# Power_Entry_24v-3pin_Fused-1A5.net
KiCad netlist of a schematic drawn in Altium Designer
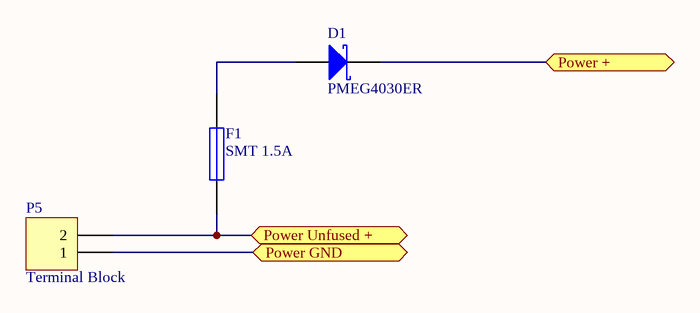
[diagram p0: Power Entry 24v-3pin Fused-1A5.SchDoc]

(export (version "E")
  (design (tool "Eeschema 10.0.6"))
  (components
    (comp (ref "D1")
      (value "PMEG4030ER")
      (footprint "SOD123W")
      (fields (field (name "VOLTAGE") "40V") (field (name "AUTHOR") "Willem Pietersz"))
      (libsource (lib "OurDb") (part "SCHOTTKY"))
    )
    (comp (ref "F1")
      (value "SMT 1.5A")
      (footprint "F_2920L185")
      (description "Fuse")
      (fields
        (field (name "PART NUMBER") "2920L185")
        (field (name "VOLTAGE") "30V")
        (field (name "PUBLISHER") "Altium Limited")
      )
      (libsource (lib "OurDb") (part "Fuse 1"))
    )
    (comp (ref "P5")
      (value "Terminal Block")
      (footprint "TB2_3.5")
      (description "Con1x2")
      (fields
        (field (name "PART NUMBER") "TB2")
        (field (name "VOLTAGE") "300")
        (field (name "AUTHOR") "Willy Pietersz")
      )
      (libsource (lib "OurDb") (part "Con1x2"))
    )
  )
  (nets
    (net (code "1") (name "/Power +") (class "Default")
      (node (ref "D1") (pin "2") (pinfunction "2_2") (pintype "passive"))
    )
    (net (code "2") (name "/Power GND") (class "Default")
      (node (ref "P5") (pin "1") (pinfunction "1_1") (pintype "passive"))
    )
    (net (code "3") (name "/Power Unfused +") (class "Default")
      (node (ref "F1") (pin "1") (pinfunction "1_1") (pintype "passive"))
      (node (ref "P5") (pin "2") (pinfunction "2_2") (pintype "passive"))
    )
    (net (code "4") (name "Net-(D1-Pad1)") (class "Default")
      (node (ref "D1") (pin "1") (pinfunction "1_1") (pintype "passive"))
      (node (ref "F1") (pin "2") (pinfunction "2_2") (pintype "passive"))
    )
  )
)
